# macropad.net
KiCad netlist of a schematic drawn in Altium Designer
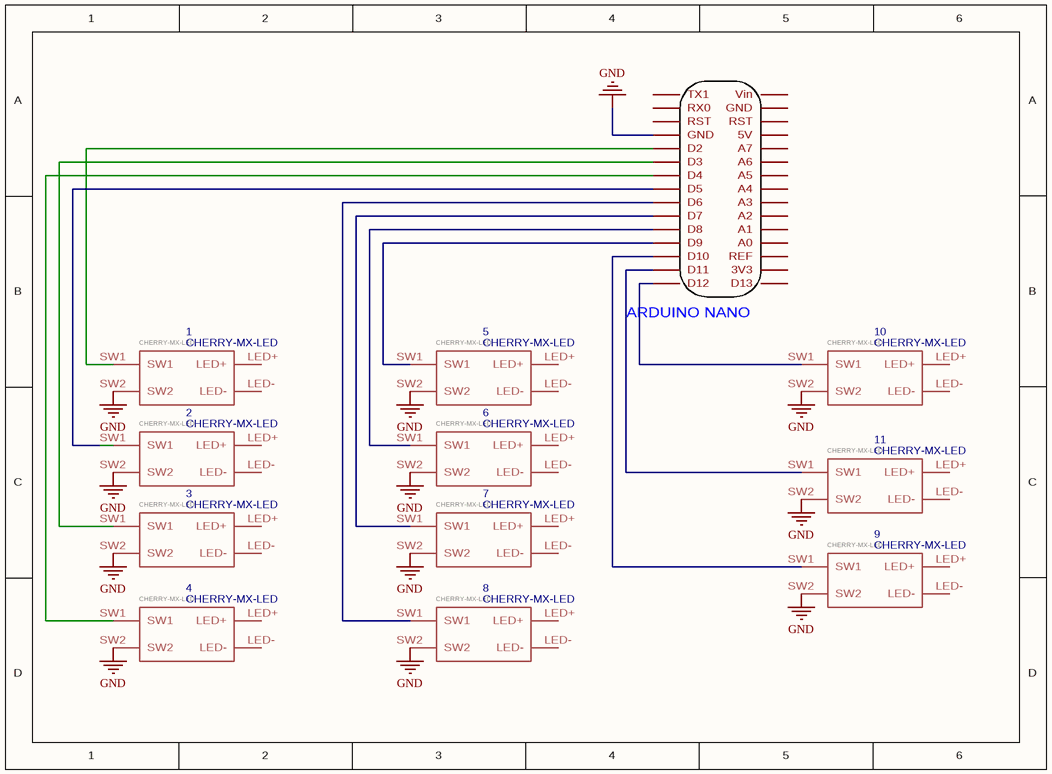
[diagram p0: macropad.schdoc]

(export (version "E")
  (design (tool "Eeschema 10.0.6"))
  (components
    (comp (ref "1")
      (value "CHERRY-MX-LED")
      (footprint "CHERRY-MX-LED")
      (fields (field (name "CONTRIBUTOR") "spaceman35"))
      (libsource (lib "altium-import") (part "root_0_CHERRY-MX-LED_"))
    )
    (comp (ref "2")
      (value "CHERRY-MX-LED")
      (footprint "CHERRY-MX-LED")
      (fields (field (name "CONTRIBUTOR") "spaceman35"))
      (libsource (lib "altium-import") (part "root_0_CHERRY-MX-LED_"))
    )
    (comp (ref "3")
      (value "CHERRY-MX-LED")
      (footprint "CHERRY-MX-LED")
      (fields (field (name "CONTRIBUTOR") "spaceman35"))
      (libsource (lib "altium-import") (part "root_0_CHERRY-MX-LED_"))
    )
    (comp (ref "4")
      (value "CHERRY-MX-LED")
      (footprint "CHERRY-MX-LED")
      (fields (field (name "CONTRIBUTOR") "spaceman35"))
      (libsource (lib "altium-import") (part "root_0_CHERRY-MX-LED_"))
    )
    (comp (ref "5")
      (value "CHERRY-MX-LED")
      (footprint "CHERRY-MX-LED")
      (fields (field (name "CONTRIBUTOR") "spaceman35"))
      (libsource (lib "altium-import") (part "root_0_CHERRY-MX-LED_"))
    )
    (comp (ref "6")
      (value "CHERRY-MX-LED")
      (footprint "CHERRY-MX-LED")
      (fields (field (name "CONTRIBUTOR") "spaceman35"))
      (libsource (lib "altium-import") (part "root_0_CHERRY-MX-LED_"))
    )
    (comp (ref "7")
      (value "CHERRY-MX-LED")
      (footprint "CHERRY-MX-LED")
      (fields (field (name "CONTRIBUTOR") "spaceman35"))
      (libsource (lib "altium-import") (part "root_0_CHERRY-MX-LED_"))
    )
    (comp (ref "8")
      (value "CHERRY-MX-LED")
      (footprint "CHERRY-MX-LED")
      (fields (field (name "CONTRIBUTOR") "spaceman35"))
      (libsource (lib "altium-import") (part "root_0_CHERRY-MX-LED_"))
    )
    (comp (ref "9")
      (value "CHERRY-MX-LED")
      (footprint "CHERRY-MX-LED")
      (fields (field (name "CONTRIBUTOR") "spaceman35"))
      (libsource (lib "altium-import") (part "root_0_CHERRY-MX-LED_"))
    )
    (comp (ref "10")
      (value "CHERRY-MX-LED")
      (footprint "CHERRY-MX-LED")
      (fields (field (name "CONTRIBUTOR") "spaceman35"))
      (libsource (lib "altium-import") (part "root_0_CHERRY-MX-LED_"))
    )
    (comp (ref "11")
      (value "CHERRY-MX-LED")
      (footprint "CHERRY-MX-LED")
      (fields (field (name "CONTRIBUTOR") "spaceman35"))
      (libsource (lib "altium-import") (part "root_0_CHERRY-MX-LED_"))
    )
    (comp (ref "M1")
      (value "Arduino Nano")
      (footprint "ARDUINO NANO")
      (fields (field (name "CONTRIBUTOR") "hctan22"))
      (libsource (lib "altium-import") (part "root_0_Arduino Nano_"))
    )
  )
  (nets
    (net (code "1") (name "GND") (class "Default")
      (node (ref "1") (pin "SW2") (pinfunction "SW2_SW2") (pintype "passive"))
      (node (ref "10") (pin "SW2") (pinfunction "SW2_SW2") (pintype "passive"))
      (node (ref "11") (pin "SW2") (pinfunction "SW2_SW2") (pintype "passive"))
      (node (ref "2") (pin "SW2") (pinfunction "SW2_SW2") (pintype "passive"))
      (node (ref "3") (pin "SW2") (pinfunction "SW2_SW2") (pintype "passive"))
      (node (ref "4") (pin "SW2") (pinfunction "SW2_SW2") (pintype "passive"))
      (node (ref "5") (pin "SW2") (pinfunction "SW2_SW2") (pintype "passive"))
      (node (ref "6") (pin "SW2") (pinfunction "SW2_SW2") (pintype "passive"))
      (node (ref "7") (pin "SW2") (pinfunction "SW2_SW2") (pintype "passive"))
      (node (ref "8") (pin "SW2") (pinfunction "SW2_SW2") (pintype "passive"))
      (node (ref "9") (pin "SW2") (pinfunction "SW2_SW2") (pintype "passive"))
      (node (ref "M1") (pin "27") (pinfunction "GND_27") (pintype "passive"))
    )
    (net (code "2") (name "Net-(M1-D2)") (class "Default")
      (node (ref "1") (pin "SW1") (pinfunction "SW1_SW1") (pintype "passive"))
      (node (ref "M1") (pin "26") (pinfunction "D2_26") (pintype "passive"))
    )
    (net (code "3") (name "Net-(M1-D3)") (class "Default")
      (node (ref "3") (pin "SW1") (pinfunction "SW1_SW1") (pintype "passive"))
      (node (ref "M1") (pin "25") (pinfunction "D3_25") (pintype "passive"))
    )
    (net (code "4") (name "Net-(M1-D4)") (class "Default")
      (node (ref "4") (pin "SW1") (pinfunction "SW1_SW1") (pintype "passive"))
      (node (ref "M1") (pin "24") (pinfunction "D4_24") (pintype "passive"))
    )
    (net (code "5") (name "Net-(M1-D5)") (class "Default")
      (node (ref "2") (pin "SW1") (pinfunction "SW1_SW1") (pintype "passive"))
      (node (ref "M1") (pin "23") (pinfunction "D5_23") (pintype "passive"))
    )
    (net (code "6") (name "Net-(M1-D6)") (class "Default")
      (node (ref "8") (pin "SW1") (pinfunction "SW1_SW1") (pintype "passive"))
      (node (ref "M1") (pin "22") (pinfunction "D6_22") (pintype "passive"))
    )
    (net (code "7") (name "Net-(M1-D7)") (class "Default")
      (node (ref "7") (pin "SW1") (pinfunction "SW1_SW1") (pintype "passive"))
      (node (ref "M1") (pin "21") (pinfunction "D7_21") (pintype "passive"))
    )
    (net (code "8") (name "Net-(M1-D8)") (class "Default")
      (node (ref "6") (pin "SW1") (pinfunction "SW1_SW1") (pintype "passive"))
      (node (ref "M1") (pin "20") (pinfunction "D8_20") (pintype "passive"))
    )
    (net (code "9") (name "Net-(M1-D9)") (class "Default")
      (node (ref "5") (pin "SW1") (pinfunction "SW1_SW1") (pintype "passive"))
      (node (ref "M1") (pin "19") (pinfunction "D9_19") (pintype "passive"))
    )
    (net (code "10") (name "Net-(M1-D10)") (class "Default")
      (node (ref "9") (pin "SW1") (pinfunction "SW1_SW1") (pintype "passive"))
      (node (ref "M1") (pin "18") (pinfunction "D10_18") (pintype "passive"))
    )
    (net (code "11") (name "Net-(M1-D11)") (class "Default")
      (node (ref "11") (pin "SW1") (pinfunction "SW1_SW1") (pintype "passive"))
      (node (ref "M1") (pin "17") (pinfunction "D11_17") (pintype "passive"))
    )
    (net (code "12") (name "Net-(M1-D12)") (class "Default")
      (node (ref "10") (pin "SW1") (pinfunction "SW1_SW1") (pintype "passive"))
      (node (ref "M1") (pin "16") (pinfunction "D12_16") (pintype "passive"))
    )
    (net (code "13") (name "unconnected-(1-PadLED+)") (class "Default")
      (node (ref "1") (pin "LED+") (pinfunction "LED+_LED+") (pintype "passive"))
    )
    (net (code "14") (name "unconnected-(1-PadLED-)") (class "Default")
      (node (ref "1") (pin "LED-") (pinfunction "LED-_LED-") (pintype "passive"))
    )
    (net (code "15") (name "unconnected-(2-PadLED+)") (class "Default")
      (node (ref "2") (pin "LED+") (pinfunction "LED+_LED+") (pintype "passive"))
    )
    (net (code "16") (name "unconnected-(2-PadLED-)") (class "Default")
      (node (ref "2") (pin "LED-") (pinfunction "LED-_LED-") (pintype "passive"))
    )
    (net (code "17") (name "unconnected-(3-PadLED+)") (class "Default")
      (node (ref "3") (pin "LED+") (pinfunction "LED+_LED+") (pintype "passive"))
    )
    (net (code "18") (name "unconnected-(3-PadLED-)") (class "Default")
      (node (ref "3") (pin "LED-") (pinfunction "LED-_LED-") (pintype "passive"))
    )
    (net (code "19") (name "unconnected-(4-PadLED+)") (class "Default")
      (node (ref "4") (pin "LED+") (pinfunction "LED+_LED+") (pintype "passive"))
    )
    (net (code "20") (name "unconnected-(4-PadLED-)") (class "Default")
      (node (ref "4") (pin "LED-") (pinfunction "LED-_LED-") (pintype "passive"))
    )
    (net (code "21") (name "unconnected-(5-PadLED+)") (class "Default")
      (node (ref "5") (pin "LED+") (pinfunction "LED+_LED+") (pintype "passive"))
    )
    (net (code "22") (name "unconnected-(5-PadLED-)") (class "Default")
      (node (ref "5") (pin "LED-") (pinfunction "LED-_LED-") (pintype "passive"))
    )
    (net (code "23") (name "unconnected-(6-PadLED+)") (class "Default")
      (node (ref "6") (pin "LED+") (pinfunction "LED+_LED+") (pintype "passive"))
    )
    (net (code "24") (name "unconnected-(6-PadLED-)") (class "Default")
      (node (ref "6") (pin "LED-") (pinfunction "LED-_LED-") (pintype "passive"))
    )
    (net (code "25") (name "unconnected-(7-PadLED+)") (class "Default")
      (node (ref "7") (pin "LED+") (pinfunction "LED+_LED+") (pintype "passive"))
    )
    (net (code "26") (name "unconnected-(7-PadLED-)") (class "Default")
      (node (ref "7") (pin "LED-") (pinfunction "LED-_LED-") (pintype "passive"))
    )
    (net (code "27") (name "unconnected-(8-PadLED+)") (class "Default")
      (node (ref "8") (pin "LED+") (pinfunction "LED+_LED+") (pintype "passive"))
    )
    (net (code "28") (name "unconnected-(8-PadLED-)") (class "Default")
      (node (ref "8") (pin "LED-") (pinfunction "LED-_LED-") (pintype "passive"))
    )
    (net (code "29") (name "unconnected-(9-PadLED+)") (class "Default")
      (node (ref "9") (pin "LED+") (pinfunction "LED+_LED+") (pintype "passive"))
    )
    (net (code "30") (name "unconnected-(9-PadLED-)") (class "Default")
      (node (ref "9") (pin "LED-") (pinfunction "LED-_LED-") (pintype "passive"))
    )
    (net (code "31") (name "unconnected-(10-PadLED+)") (class "Default")
      (node (ref "10") (pin "LED+") (pinfunction "LED+_LED+") (pintype "passive"))
    )
    (net (code "32") (name "unconnected-(10-PadLED-)") (class "Default")
      (node (ref "10") (pin "LED-") (pinfunction "LED-_LED-") (pintype "passive"))
    )
    (net (code "33") (name "unconnected-(11-PadLED+)") (class "Default")
      (node (ref "11") (pin "LED+") (pinfunction "LED+_LED+") (pintype "passive"))
    )
    (net (code "34") (name "unconnected-(11-PadLED-)") (class "Default")
      (node (ref "11") (pin "LED-") (pinfunction "LED-_LED-") (pintype "passive"))
    )
    (net (code "35") (name "unconnected-(M1-3V3-Pad14)") (class "Default")
      (node (ref "M1") (pin "14") (pinfunction "3V3_14") (pintype "passive"))
    )
    (net (code "36") (name "unconnected-(M1-5V-Pad4)") (class "Default")
      (node (ref "M1") (pin "4") (pinfunction "5V_4") (pintype "passive"))
    )
    (net (code "37") (name "unconnected-(M1-A0-Pad12)") (class "Default")
      (node (ref "M1") (pin "12") (pinfunction "A0_12") (pintype "passive"))
    )
    (net (code "38") (name "unconnected-(M1-A1-Pad11)") (class "Default")
      (node (ref "M1") (pin "11") (pinfunction "A1_11") (pintype "passive"))
    )
    (net (code "39") (name "unconnected-(M1-A2-Pad10)") (class "Default")
      (node (ref "M1") (pin "10") (pinfunction "A2_10") (pintype "passive"))
    )
    (net (code "40") (name "unconnected-(M1-A3-Pad9)") (class "Default")
      (node (ref "M1") (pin "9") (pinfunction "A3_9") (pintype "passive"))
    )
    (net (code "41") (name "unconnected-(M1-A4-Pad8)") (class "Default")
      (node (ref "M1") (pin "8") (pinfunction "A4_8") (pintype "passive"))
    )
    (net (code "42") (name "unconnected-(M1-A5-Pad7)") (class "Default")
      (node (ref "M1") (pin "7") (pinfunction "A5_7") (pintype "passive"))
    )
    (net (code "43") (name "unconnected-(M1-A6-Pad6)") (class "Default")
      (node (ref "M1") (pin "6") (pinfunction "A6_6") (pintype "passive"))
    )
    (net (code "44") (name "unconnected-(M1-A7-Pad5)") (class "Default")
      (node (ref "M1") (pin "5") (pinfunction "A7_5") (pintype "passive"))
    )
    (net (code "45") (name "unconnected-(M1-D13-Pad15)") (class "Default")
      (node (ref "M1") (pin "15") (pinfunction "D13_15") (pintype "passive"))
    )
    (net (code "46") (name "unconnected-(M1-GND-Pad2)") (class "Default")
      (node (ref "M1") (pin "2") (pinfunction "GND_2") (pintype "passive"))
    )
    (net (code "47") (name "unconnected-(M1-REF-Pad13)") (class "Default")
      (node (ref "M1") (pin "13") (pinfunction "REF_13") (pintype "passive"))
    )
    (net (code "48") (name "unconnected-(M1-RST-Pad3)") (class "Default")
      (node (ref "M1") (pin "3") (pinfunction "RST_3") (pintype "passive"))
    )
    (net (code "49") (name "unconnected-(M1-RST-Pad28)") (class "Default")
      (node (ref "M1") (pin "28") (pinfunction "RST_28") (pintype "passive"))
    )
    (net (code "50") (name "unconnected-(M1-RX0-Pad29)") (class "Default")
      (node (ref "M1") (pin "29") (pinfunction "RX0_29") (pintype "passive"))
    )
    (net (code "51") (name "unconnected-(M1-TX1-Pad30)") (class "Default")
      (node (ref "M1") (pin "30") (pinfunction "TX1_30") (pintype "passive"))
    )
    (net (code "52") (name "unconnected-(M1-Vin-Pad1)") (class "Default")
      (node (ref "M1") (pin "1") (pinfunction "Vin_1") (pintype "passive"))
    )
  )
)
